# chaoswest-token.net
KiCad netlist of a schematic drawn in EAGLE
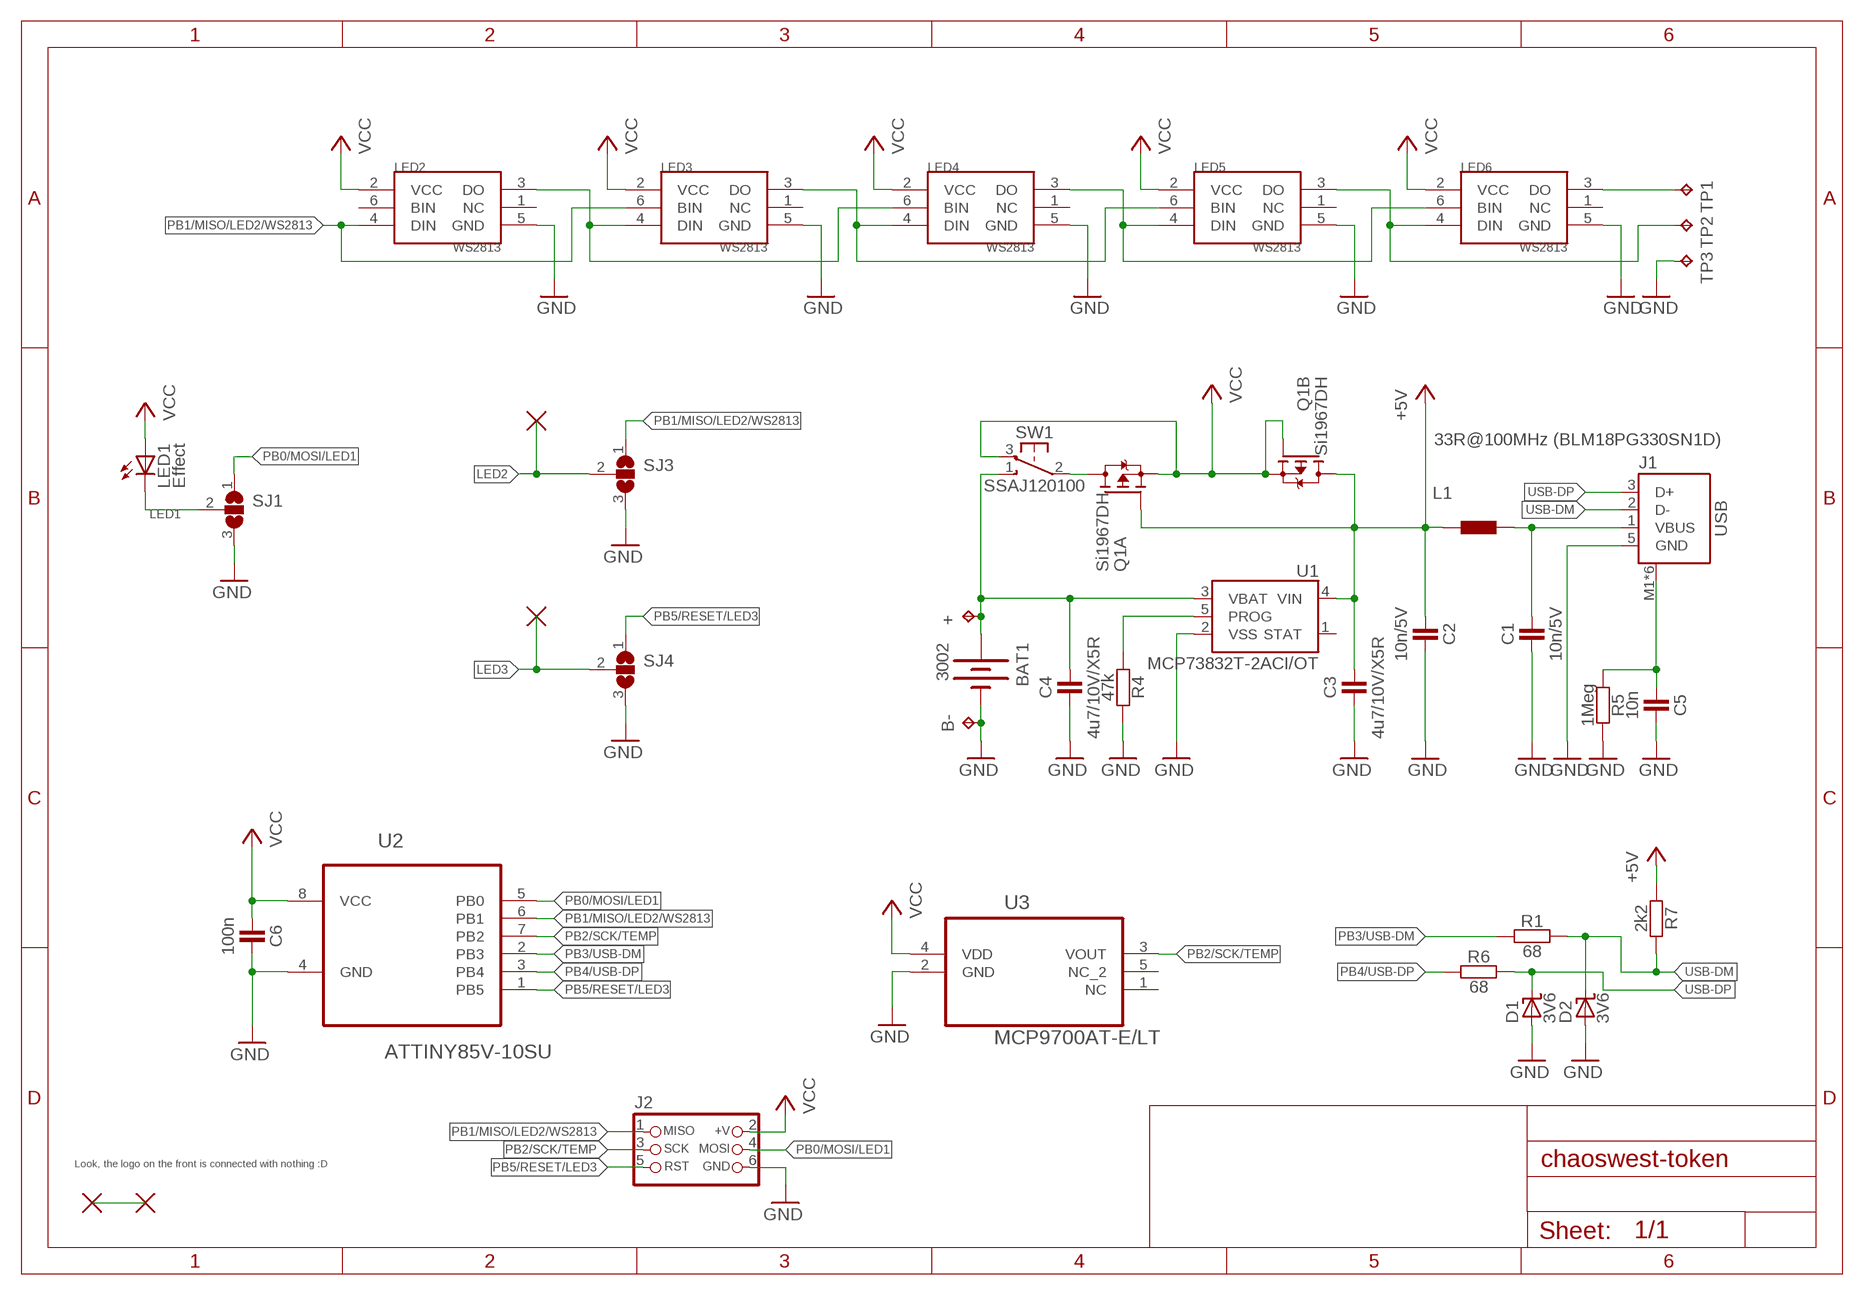
[diagram p0: schematic, sheet 1]

(export (version "E")
  (design (tool "Eeschema 10.0.6"))
  (components
    (comp (ref "+")
      (value "TPTP18SQ")
      (footprint "eagle-import:TP18SQ")
      (libsource (lib "eagle-import") (part "TPTP18SQ"))
    )
    (comp (ref "B-")
      (value "TPTP18SQ")
      (footprint "eagle-import:TP18SQ")
      (libsource (lib "eagle-import") (part "TPTP18SQ"))
    )
    (comp (ref "BAT1")
      (value "3002")
      (footprint "eagle-import:BATTCON_20MM")
      (libsource (lib "eagle-import") (part "3002"))
    )
    (comp (ref "C1")
      (value "10n/5V")
      (footprint "eagle-import:C0805")
      (libsource (lib "eagle-import") (part "CAPACITOR-0805"))
    )
    (comp (ref "C2")
      (value "10n/5V")
      (footprint "eagle-import:C0805")
      (libsource (lib "eagle-import") (part "CAPACITOR-0805"))
    )
    (comp (ref "C3")
      (value "4u7/10V/X5R")
      (footprint "eagle-import:C0805")
      (libsource (lib "eagle-import") (part "CAPACITOR-0805"))
    )
    (comp (ref "C4")
      (value "4u7/10V/X5R")
      (footprint "eagle-import:C0805")
      (libsource (lib "eagle-import") (part "CAPACITOR-0805"))
    )
    (comp (ref "C5")
      (value "10n")
      (footprint "eagle-import:C0805")
      (libsource (lib "eagle-import") (part "CAPACITOR-0805"))
    )
    (comp (ref "C6")
      (value "100n")
      (footprint "eagle-import:C0805")
      (libsource (lib "eagle-import") (part "CAPACITOR-0805"))
    )
    (comp (ref "D1")
      (value "3V6")
      (footprint "eagle-import:SOD123")
      (libsource (lib "eagle-import") (part "D_ZENER-SOD123"))
    )
    (comp (ref "D2")
      (value "3V6")
      (footprint "eagle-import:SOD123")
      (libsource (lib "eagle-import") (part "D_ZENER-SOD123"))
    )
    (comp (ref "J1")
      (value "USB")
      (footprint "eagle-import:MOLEX_47346-0001")
      (fields (field (name "MPN") "47346-0001"))
      (libsource (lib "eagle-import") (part "47346-0001"))
    )
    (comp (ref "J2")
      (value "ISP")
      (footprint "eagle-import:M2X3_SMD")
      (libsource (lib "eagle-import") (part "CON_HEADER_PRG_AVR_ICSP-SMD"))
    )
    (comp (ref "L1")
      (value "33R@100MHz (BLM18PG330SN1D)")
      (footprint "eagle-import:C0805")
      (libsource (lib "eagle-import") (part "INDUCTOR-0805"))
    )
    (comp (ref "LED1")
      (value "Effect")
      (footprint "eagle-import:LED5MM")
      (libsource (lib "eagle-import") (part "LED5MM"))
    )
    (comp (ref "LED2")
      (value "WS2813")
      (footprint "eagle-import:WS2813")
      (libsource (lib "eagle-import") (part "WS2813"))
    )
    (comp (ref "LED3")
      (value "WS2813")
      (footprint "eagle-import:WS2813")
      (libsource (lib "eagle-import") (part "WS2813"))
    )
    (comp (ref "LED4")
      (value "WS2813")
      (footprint "eagle-import:WS2813")
      (libsource (lib "eagle-import") (part "WS2813"))
    )
    (comp (ref "LED5")
      (value "WS2813")
      (footprint "eagle-import:WS2813")
      (libsource (lib "eagle-import") (part "WS2813"))
    )
    (comp (ref "LED6")
      (value "WS2813")
      (footprint "eagle-import:WS2813")
      (libsource (lib "eagle-import") (part "WS2813"))
    )
    (comp (ref "Q1")
      (value "Si1967DH")
      (footprint "eagle-import:SOT363")
      (libsource (lib "eagle-import") (part "BSS84AKS"))
    )
    (comp (ref "R1")
      (value "68")
      (footprint "eagle-import:C0805")
      (libsource (lib "eagle-import") (part "RESISTOR-0805"))
    )
    (comp (ref "R4")
      (value "47k")
      (footprint "eagle-import:C0805")
      (libsource (lib "eagle-import") (part "RESISTOR-0805"))
    )
    (comp (ref "R5")
      (value "1Meg")
      (footprint "eagle-import:C0805")
      (libsource (lib "eagle-import") (part "RESISTOR-0805"))
    )
    (comp (ref "R6")
      (value "68")
      (footprint "eagle-import:C0805")
      (libsource (lib "eagle-import") (part "RESISTOR-0805"))
    )
    (comp (ref "R7")
      (value "2k2")
      (footprint "eagle-import:C0805")
      (libsource (lib "eagle-import") (part "RESISTOR-0805"))
    )
    (comp (ref "SJ1")
      (value "SJ2W")
      (footprint "eagle-import:SJ_2")
      (libsource (lib "eagle-import") (part "SJ2W"))
    )
    (comp (ref "SJ3")
      (value "SJ2W")
      (footprint "eagle-import:SJ_2")
      (libsource (lib "eagle-import") (part "SJ2W"))
    )
    (comp (ref "SJ4")
      (value "SJ2W")
      (footprint "eagle-import:SJ_2")
      (libsource (lib "eagle-import") (part "SJ2W"))
    )
    (comp (ref "SW1")
      (value "SSAJ120100")
      (footprint "eagle-import:SSAJ120100")
      (libsource (lib "eagle-import") (part "SSAJ120100"))
    )
    (comp (ref "TP1")
      (value "DO")
      (footprint "eagle-import:TP09SQ")
      (libsource (lib "eagle-import") (part "TPTP09SQ"))
    )
    (comp (ref "TP2")
      (value "BO")
      (footprint "eagle-import:TP09SQ")
      (libsource (lib "eagle-import") (part "TPTP09SQ"))
    )
    (comp (ref "TP3")
      (value "GND")
      (footprint "eagle-import:TP09SQ")
      (libsource (lib "eagle-import") (part "TPTP09SQ"))
    )
    (comp (ref "U$1")
      (value "EMPTY_SIGNAL")
      (footprint "eagle-import:SMALLSPOT")
      (libsource (lib "eagle-import") (part "EMPTY_SIGNAL"))
    )
    (comp (ref "U$2")
      (value "EMPTY_SIGNAL")
      (footprint "eagle-import:SMALLSPOT")
      (libsource (lib "eagle-import") (part "EMPTY_SIGNAL"))
    )
    (comp (ref "U$3")
      (value "EMPTY_SIGNAL")
      (footprint "eagle-import:SMALLSPOT")
      (libsource (lib "eagle-import") (part "EMPTY_SIGNAL"))
    )
    (comp (ref "U$4")
      (value "EMPTY_SIGNAL")
      (footprint "eagle-import:SMALLSPOT")
      (libsource (lib "eagle-import") (part "EMPTY_SIGNAL"))
    )
    (comp (ref "U1")
      (value "MCP73832T-2ACI/OT")
      (footprint "eagle-import:SOT23-5")
      (libsource (lib "eagle-import") (part "MCP73831"))
    )
    (comp (ref "U2")
      (value "ATTINY85V-10SU")
      (footprint "eagle-import:SOIC127P798X216-8N")
      (libsource (lib "eagle-import") (part "ATTINY85V-10SU"))
    )
    (comp (ref "U3")
      (value "MCP9700AT-E/LT")
      (footprint "eagle-import:SOT65P210X110-5N")
      (libsource (lib "eagle-import") (part "MCP9700AT-E/LT"))
    )
  )
  (nets
    (net (code "1") (name "+5V") (class "Default")
      (node (ref "C2") (pin "1") (pinfunction "1_1") (pintype "passive"))
      (node (ref "C3") (pin "1") (pinfunction "1_1") (pintype "passive"))
      (node (ref "L1") (pin "2") (pinfunction "2_2") (pintype "passive"))
      (node (ref "Q1") (pin "2") (pinfunction "G_2") (pintype "passive"))
      (node (ref "Q1") (pin "3") (pinfunction "D_3") (pintype "passive"))
      (node (ref "R7") (pin "2") (pinfunction "2_2") (pintype "passive"))
      (node (ref "U1") (pin "4") (pinfunction "VIN_4") (pintype "power_in"))
    )
    (net (code "2") (name "/LED1") (class "Default")
      (node (ref "LED1") (pin "K") (pinfunction "C_K") (pintype "passive"))
      (node (ref "SJ1") (pin "2") (pinfunction "2_2") (pintype "passive"))
    )
    (net (code "3") (name "GND") (class "Default")
      (node (ref "B-") (pin "TP") (pinfunction "TP_TP") (pintype "input"))
      (node (ref "BAT1") (pin "-") (pinfunction "-_-") (pintype "power_in"))
      (node (ref "C1") (pin "2") (pinfunction "2_2") (pintype "passive"))
      (node (ref "C2") (pin "2") (pinfunction "2_2") (pintype "passive"))
      (node (ref "C3") (pin "2") (pinfunction "2_2") (pintype "passive"))
      (node (ref "C4") (pin "2") (pinfunction "2_2") (pintype "passive"))
      (node (ref "C5") (pin "2") (pinfunction "2_2") (pintype "passive"))
      (node (ref "C6") (pin "2") (pinfunction "2_2") (pintype "passive"))
      (node (ref "D1") (pin "A") (pinfunction "A_A") (pintype "passive"))
      (node (ref "D2") (pin "A") (pinfunction "A_A") (pintype "passive"))
      (node (ref "J1") (pin "5") (pinfunction "GND_5") (pintype "power_in"))
      (node (ref "J2") (pin "6") (pinfunction "GND_6") (pintype "passive"))
      (node (ref "LED2") (pin "5") (pinfunction "GND_5") (pintype "power_in"))
      (node (ref "LED3") (pin "5") (pinfunction "GND_5") (pintype "power_in"))
      (node (ref "LED4") (pin "5") (pinfunction "GND_5") (pintype "power_in"))
      (node (ref "LED5") (pin "5") (pinfunction "GND_5") (pintype "power_in"))
      (node (ref "LED6") (pin "5") (pinfunction "GND_5") (pintype "power_in"))
      (node (ref "R4") (pin "1") (pinfunction "1_1") (pintype "passive"))
      (node (ref "R5") (pin "1") (pinfunction "1_1") (pintype "passive"))
      (node (ref "SJ1") (pin "3") (pinfunction "3_3") (pintype "passive"))
      (node (ref "SJ3") (pin "3") (pinfunction "3_3") (pintype "passive"))
      (node (ref "SJ4") (pin "3") (pinfunction "3_3") (pintype "passive"))
      (node (ref "TP3") (pin "TP") (pinfunction "TP_TP") (pintype "input"))
      (node (ref "U1") (pin "2") (pinfunction "VSS_2") (pintype "power_in"))
      (node (ref "U2") (pin "4") (pinfunction "GND_4") (pintype "passive"))
      (node (ref "U3") (pin "2") (pinfunction "GND_2") (pintype "passive"))
    )
    (net (code "4") (name "LED2") (class "Default")
      (node (ref "SJ3") (pin "2") (pinfunction "2_2") (pintype "passive"))
      (node (ref "U$3") (pin "X") (pinfunction "X_X") (pintype "bidirectional"))
    )
    (net (code "5") (name "LED3") (class "Default")
      (node (ref "SJ4") (pin "2") (pinfunction "2_2") (pintype "passive"))
      (node (ref "U$4") (pin "X") (pinfunction "X_X") (pintype "bidirectional"))
    )
    (net (code "6") (name "Net-(C5-Pad1)") (class "Default")
      (node (ref "C5") (pin "1") (pinfunction "1_1") (pintype "passive"))
      (node (ref "J1") (pin "M1") (pinfunction "SHIELD_M1") (pintype "passive"))
      (node (ref "J1") (pin "M2") (pinfunction "SHIELD_M2") (pintype "passive"))
      (node (ref "J1") (pin "M3") (pinfunction "SHIELD_M3") (pintype "passive"))
      (node (ref "J1") (pin "M4") (pinfunction "SHIELD_M4") (pintype "passive"))
      (node (ref "J1") (pin "M5") (pinfunction "SHIELD_M5") (pintype "passive"))
      (node (ref "J1") (pin "M6") (pinfunction "SHIELD_M6") (pintype "passive"))
      (node (ref "R5") (pin "2") (pinfunction "2_2") (pintype "passive"))
    )
    (net (code "7") (name "Net-(J1-VBUS)") (class "Default")
      (node (ref "C1") (pin "1") (pinfunction "1_1") (pintype "passive"))
      (node (ref "J1") (pin "1") (pinfunction "VBUS_1") (pintype "power_in"))
      (node (ref "L1") (pin "1") (pinfunction "1_1") (pintype "passive"))
    )
    (net (code "8") (name "Net-(LED2-DO)") (class "Default")
      (node (ref "LED2") (pin "3") (pinfunction "DO_3") (pintype "bidirectional"))
      (node (ref "LED3") (pin "4") (pinfunction "DIN_4") (pintype "bidirectional"))
      (node (ref "LED4") (pin "6") (pinfunction "BIN_6") (pintype "bidirectional"))
    )
    (net (code "9") (name "Net-(LED3-DO)") (class "Default")
      (node (ref "LED3") (pin "3") (pinfunction "DO_3") (pintype "bidirectional"))
      (node (ref "LED4") (pin "4") (pinfunction "DIN_4") (pintype "bidirectional"))
      (node (ref "LED5") (pin "6") (pinfunction "BIN_6") (pintype "bidirectional"))
    )
    (net (code "10") (name "Net-(LED4-DO)") (class "Default")
      (node (ref "LED4") (pin "3") (pinfunction "DO_3") (pintype "bidirectional"))
      (node (ref "LED5") (pin "4") (pinfunction "DIN_4") (pintype "bidirectional"))
      (node (ref "LED6") (pin "6") (pinfunction "BIN_6") (pintype "bidirectional"))
    )
    (net (code "11") (name "Net-(LED5-DO)") (class "Default")
      (node (ref "LED5") (pin "3") (pinfunction "DO_3") (pintype "bidirectional"))
      (node (ref "LED6") (pin "4") (pinfunction "DIN_4") (pintype "bidirectional"))
      (node (ref "TP2") (pin "TP") (pinfunction "TP_TP") (pintype "input"))
    )
    (net (code "12") (name "Net-(LED6-DO)") (class "Default")
      (node (ref "LED6") (pin "3") (pinfunction "DO_3") (pintype "bidirectional"))
      (node (ref "TP1") (pin "TP") (pinfunction "TP_TP") (pintype "input"))
    )
    (net (code "13") (name "Net-(Q1A-D)") (class "Default")
      (node (ref "Q1") (pin "6") (pinfunction "D_6") (pintype "passive"))
      (node (ref "SW1") (pin "2") (pinfunction "P1_2") (pintype "passive"))
    )
    (net (code "14") (name "Net-(SW1-S1)") (class "Default")
      (node (ref "+") (pin "TP") (pinfunction "TP_TP") (pintype "input"))
      (node (ref "BAT1") (pin "+1") (pinfunction "+_+1") (pintype "power_in"))
      (node (ref "BAT1") (pin "+2") (pinfunction "+_+2") (pintype "power_in"))
      (node (ref "C4") (pin "1") (pinfunction "1_1") (pintype "passive"))
      (node (ref "SW1") (pin "1") (pinfunction "S1_1") (pintype "passive"))
      (node (ref "U1") (pin "3") (pinfunction "VBAT_3") (pintype "power_in"))
    )
    (net (code "15") (name "Net-(U$1-PadX)") (class "Default")
      (node (ref "U$1") (pin "X") (pinfunction "X_X") (pintype "bidirectional"))
      (node (ref "U$2") (pin "X") (pinfunction "X_X") (pintype "bidirectional"))
    )
    (net (code "16") (name "Net-(U1-PROG)") (class "Default")
      (node (ref "R4") (pin "2") (pinfunction "2_2") (pintype "passive"))
      (node (ref "U1") (pin "5") (pinfunction "PROG_5") (pintype "input"))
    )
    (net (code "17") (name "PB0{slash}MOSI{slash}LED1") (class "Default")
      (node (ref "J2") (pin "4") (pinfunction "MOSI_4") (pintype "passive"))
      (node (ref "SJ1") (pin "1") (pinfunction "1_1") (pintype "passive"))
      (node (ref "U2") (pin "5") (pinfunction "PB0_5") (pintype "bidirectional"))
    )
    (net (code "18") (name "PB1{slash}MISO{slash}LED2{slash}WS2813") (class "Default")
      (node (ref "J2") (pin "1") (pinfunction "MISO_1") (pintype "passive"))
      (node (ref "LED2") (pin "4") (pinfunction "DIN_4") (pintype "bidirectional"))
      (node (ref "LED3") (pin "6") (pinfunction "BIN_6") (pintype "bidirectional"))
      (node (ref "SJ3") (pin "1") (pinfunction "1_1") (pintype "passive"))
      (node (ref "U2") (pin "6") (pinfunction "PB1_6") (pintype "bidirectional"))
    )
    (net (code "19") (name "PB2{slash}SCK{slash}TEMP") (class "Default")
      (node (ref "J2") (pin "3") (pinfunction "SCK_3") (pintype "passive"))
      (node (ref "U2") (pin "7") (pinfunction "PB2_7") (pintype "bidirectional"))
      (node (ref "U3") (pin "3") (pinfunction "VOUT_3") (pintype "output"))
    )
    (net (code "20") (name "PB3{slash}USB-DM") (class "Default")
      (node (ref "R1") (pin "2") (pinfunction "2_2") (pintype "passive"))
      (node (ref "U2") (pin "2") (pinfunction "PB3_2") (pintype "bidirectional"))
    )
    (net (code "21") (name "PB4{slash}USB-DP") (class "Default")
      (node (ref "R6") (pin "2") (pinfunction "2_2") (pintype "passive"))
      (node (ref "U2") (pin "3") (pinfunction "PB4_3") (pintype "bidirectional"))
    )
    (net (code "22") (name "PB5{slash}RESET{slash}LED3") (class "Default")
      (node (ref "J2") (pin "5") (pinfunction "RST_5") (pintype "passive"))
      (node (ref "SJ4") (pin "1") (pinfunction "1_1") (pintype "passive"))
      (node (ref "U2") (pin "1") (pinfunction "PB5_1") (pintype "bidirectional"))
    )
    (net (code "23") (name "USB-DM") (class "Default")
      (node (ref "D2") (pin "C") (pinfunction "C_C") (pintype "passive"))
      (node (ref "J1") (pin "2") (pinfunction "D-_2") (pintype "bidirectional"))
      (node (ref "R1") (pin "1") (pinfunction "1_1") (pintype "passive"))
      (node (ref "R7") (pin "1") (pinfunction "1_1") (pintype "passive"))
    )
    (net (code "24") (name "USB-DP") (class "Default")
      (node (ref "D1") (pin "C") (pinfunction "C_C") (pintype "passive"))
      (node (ref "J1") (pin "3") (pinfunction "D+_3") (pintype "bidirectional"))
      (node (ref "R6") (pin "1") (pinfunction "1_1") (pintype "passive"))
    )
    (net (code "25") (name "VCC") (class "Default")
      (node (ref "C6") (pin "1") (pinfunction "1_1") (pintype "passive"))
      (node (ref "J2") (pin "2") (pinfunction "+V_2") (pintype "passive"))
      (node (ref "LED1") (pin "A") (pinfunction "A_A") (pintype "passive"))
      (node (ref "LED2") (pin "2") (pinfunction "VCC_2") (pintype "power_in"))
      (node (ref "LED3") (pin "2") (pinfunction "VCC_2") (pintype "power_in"))
      (node (ref "LED4") (pin "2") (pinfunction "VCC_2") (pintype "power_in"))
      (node (ref "LED5") (pin "2") (pinfunction "VCC_2") (pintype "power_in"))
      (node (ref "LED6") (pin "2") (pinfunction "VCC_2") (pintype "power_in"))
      (node (ref "Q1") (pin "1") (pinfunction "S_1") (pintype "passive"))
      (node (ref "Q1") (pin "4") (pinfunction "S_4") (pintype "passive"))
      (node (ref "Q1") (pin "5") (pinfunction "G_5") (pintype "passive"))
      (node (ref "SW1") (pin "3") (pinfunction "O1_3") (pintype "passive"))
      (node (ref "U2") (pin "8") (pinfunction "VCC_8") (pintype "power_in"))
      (node (ref "U3") (pin "4") (pinfunction "VDD_4") (pintype "power_in"))
    )
    (net (code "26") (name "unconnected-(LED2-BIN-Pad6)") (class "Default")
      (node (ref "LED2") (pin "6") (pinfunction "BIN_6") (pintype "bidirectional"))
    )
    (net (code "27") (name "unconnected-(LED2-NC-Pad1)") (class "Default")
      (node (ref "LED2") (pin "1") (pinfunction "NC_1") (pintype "no_connect"))
    )
    (net (code "28") (name "unconnected-(LED3-NC-Pad1)") (class "Default")
      (node (ref "LED3") (pin "1") (pinfunction "NC_1") (pintype "no_connect"))
    )
    (net (code "29") (name "unconnected-(LED4-NC-Pad1)") (class "Default")
      (node (ref "LED4") (pin "1") (pinfunction "NC_1") (pintype "no_connect"))
    )
    (net (code "30") (name "unconnected-(LED5-NC-Pad1)") (class "Default")
      (node (ref "LED5") (pin "1") (pinfunction "NC_1") (pintype "no_connect"))
    )
    (net (code "31") (name "unconnected-(LED6-NC-Pad1)") (class "Default")
      (node (ref "LED6") (pin "1") (pinfunction "NC_1") (pintype "no_connect"))
    )
    (net (code "32") (name "unconnected-(U1-STAT-Pad1)") (class "Default")
      (node (ref "U1") (pin "1") (pinfunction "STAT_1") (pintype "output"))
    )
    (net (code "33") (name "unconnected-(U3-NC-Pad1)") (class "Default")
      (node (ref "U3") (pin "1") (pinfunction "NC_1") (pintype "no_connect"))
    )
    (net (code "34") (name "unconnected-(U3-NC_2-Pad5)") (class "Default")
      (node (ref "U3") (pin "5") (pinfunction "NC_2_5") (pintype "no_connect"))
    )
  )
)
